# Signal_Conditioner.net
KiCad netlist of a schematic drawn in Altium Designer
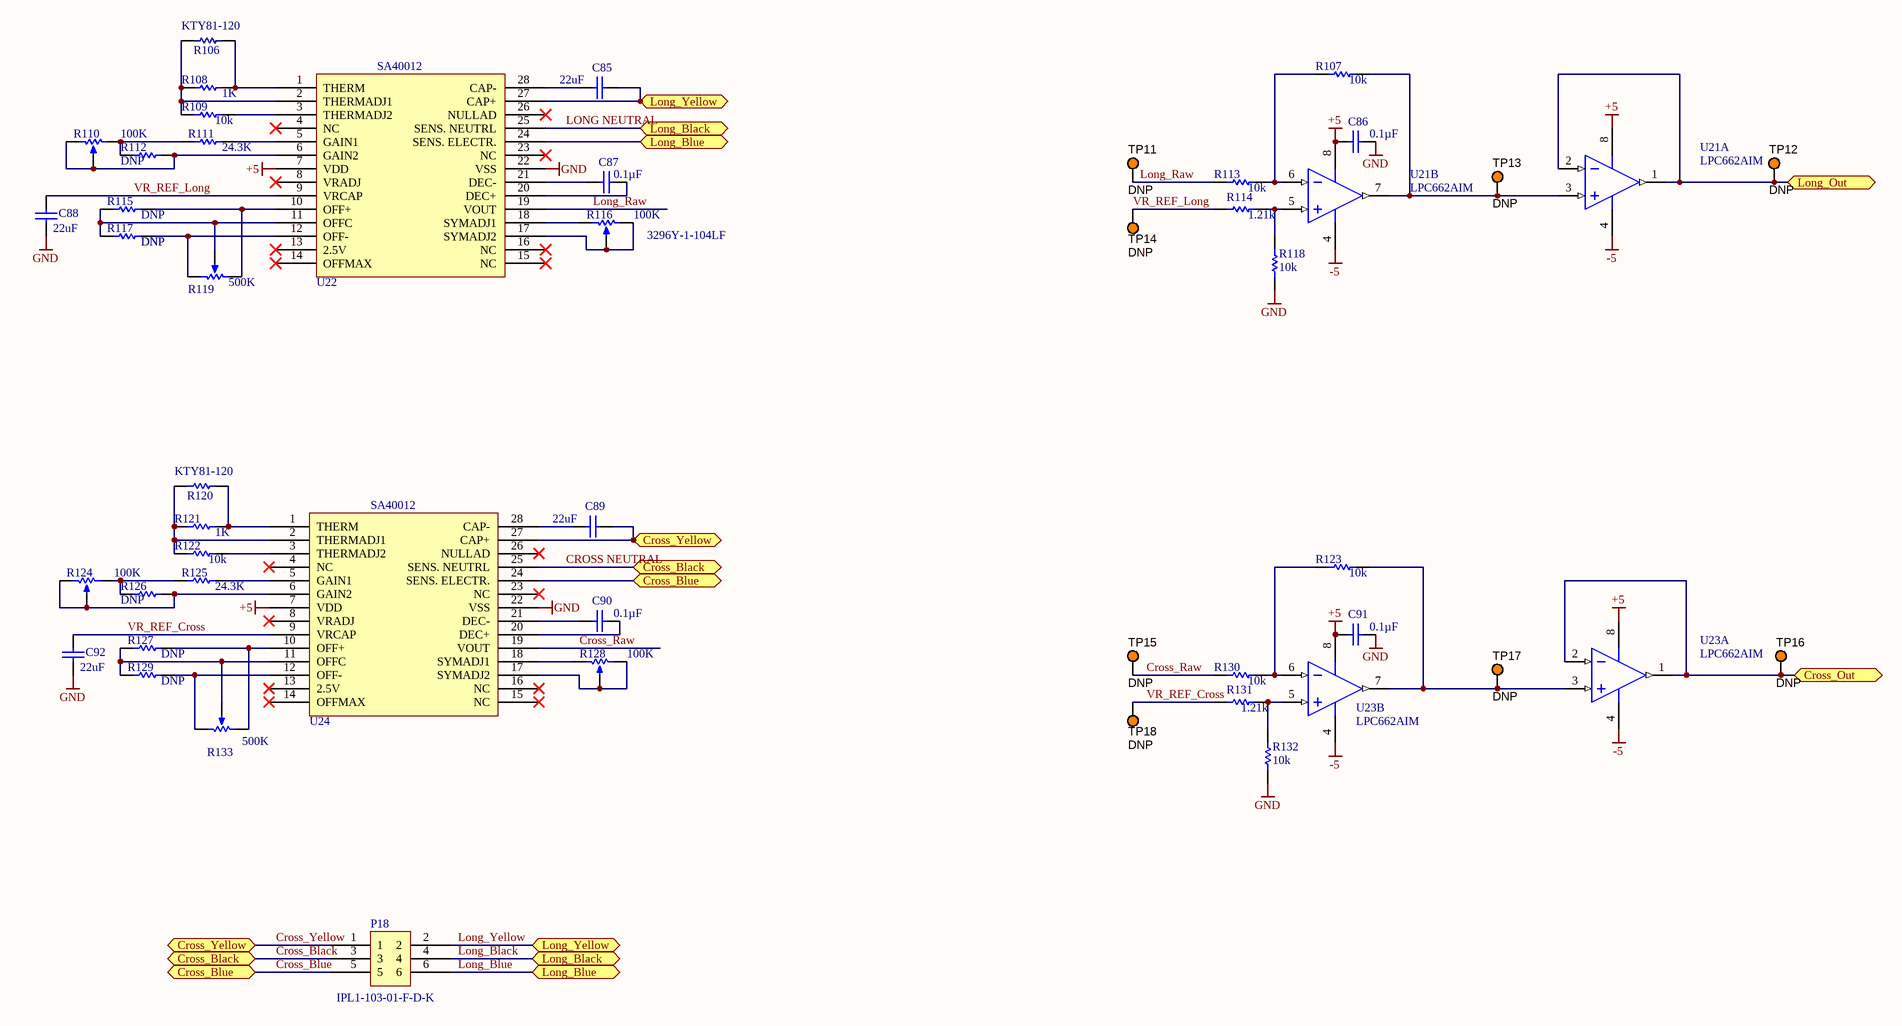
[diagram p0: Signal_Conditioner.SchDoc]

(export (version "E")
  (design (tool "Eeschema 10.0.6"))
  (components
    (comp (ref "C85")
      (value "22uF")
      (footprint "CAPC0805(2012)145_N")
      (description "CAP CER 22UF 16V X5R 0805")
      (fields
        (field (name "MANUFACTURER") "Murata Electronics North America")
        (field (name "MANUFACTURER PART NUMBER") "GRM219R61C226ME15L")
      )
      (libsource (lib "Altium Content Vault") (part "CMP-1036-04795-1"))
    )
    (comp (ref "C86")
      (value "CAP CER 0.1UF 25V X7R 0805")
      (footprint "CAPC0805(2012)145_N")
      (fields
        (field (name "MANUFACTURER") "Murata Electronics North America")
        (field (name "MANUFACTURER PART NUMBER") "GRM21BR71E104KA01L")
        (field (name "CAPACITANCE") "0.1µF")
        (field (name "TOLERANCE") "±10%")
      )
      (libsource (lib "Altium Content Vault") (part "CMP-1036-04795-1"))
    )
    (comp (ref "C87")
      (value "CAP CER 0.1UF 25V X7R 0805")
      (footprint "CAPC0805(2012)145_N")
      (fields
        (field (name "MANUFACTURER") "Murata Electronics North America")
        (field (name "MANUFACTURER PART NUMBER") "GRM21BR71E104KA01L")
        (field (name "CAPACITANCE") "0.1µF")
        (field (name "TOLERANCE") "±10%")
      )
      (libsource (lib "Altium Content Vault") (part "CMP-1036-04795-1"))
    )
    (comp (ref "C88")
      (value "22uF")
      (footprint "CAPC0805(2012)145_N")
      (description "CAP CER 22UF 16V X5R 0805")
      (fields
        (field (name "MANUFACTURER") "Murata Electronics North America")
        (field (name "MANUFACTURER PART NUMBER") "GRM219R61C226ME15L")
      )
      (libsource (lib "Altium Content Vault") (part "CMP-1036-04795-1"))
    )
    (comp (ref "C89")
      (value "22uF")
      (footprint "CAPC0805(2012)145_N")
      (description "CAP CER 22UF 16V X5R 0805")
      (fields
        (field (name "MANUFACTURER") "Murata Electronics North America")
        (field (name "MANUFACTURER PART NUMBER") "GRM219R61C226ME15L")
      )
      (libsource (lib "Altium Content Vault") (part "CMP-1036-04795-1"))
    )
    (comp (ref "C90")
      (value "CAP CER 0.1UF 25V X7R 0805")
      (footprint "CAPC0805(2012)145_N")
      (fields
        (field (name "MANUFACTURER") "Murata Electronics North America")
        (field (name "MANUFACTURER PART NUMBER") "GRM21BR71E104KA01L")
        (field (name "CAPACITANCE") "0.1µF")
        (field (name "TOLERANCE") "±10%")
      )
      (libsource (lib "Altium Content Vault") (part "CMP-1036-04795-1"))
    )
    (comp (ref "C91")
      (value "CAP CER 0.1UF 25V X7R 0805")
      (footprint "CAPC0805(2012)145_N")
      (fields
        (field (name "MANUFACTURER") "Murata Electronics North America")
        (field (name "MANUFACTURER PART NUMBER") "GRM21BR71E104KA01L")
        (field (name "CAPACITANCE") "0.1µF")
        (field (name "TOLERANCE") "±10%")
      )
      (libsource (lib "Altium Content Vault") (part "CMP-1036-04795-1"))
    )
    (comp (ref "C92")
      (value "22uF")
      (footprint "CAPC0805(2012)145_N")
      (description "CAP CER 22UF 16V X5R 0805")
      (fields
        (field (name "MANUFACTURER") "Murata Electronics North America")
        (field (name "MANUFACTURER PART NUMBER") "GRM219R61C226ME15L")
      )
      (libsource (lib "Altium Content Vault") (part "CMP-1036-04795-1"))
    )
    (comp (ref "P18")
      (value "IPL1-103-01-F-D")
      (footprint "IPL1-103-01-F-D")
      (fields
        (field (name "MANUFACTURER") "SAMTEC")
        (field (name "MANUFACTURER PART NUMBER") "IPL1-103-01-F-D-K")
        (field (name "COMPONENTLINK1URL") "https://webassistants.partcommunity.com/23d-libs/samtec/search/resolve.html?EMAIL=mysamtec@samtec.com&PN=HTSW-114-05-F-D")
        (field (name "COMPONENTLINK1DESCRIPTION") "https://webassistants.partcommunity.com/23d-libs/samtec/search/resolve.html?EMAIL=mysamtec@samtec.com&PN=HTSW-114-05-F-D")
      )
      (libsource (lib "ZLS_Schematic_lib") (part "IPL1-103-01-F-D"))
    )
    (comp (ref "R106")
      (value "KTY81-120")
      (footprint "KTY81-120")
      (description "THERMISTOR PTC 1K OHM PBCYT2")
      (fields
        (field (name "MANUFACTURER") "NXP USA Inc.")
        (field (name "MANUFACTURER PART NUMBER") "KTY81/120,112")
      )
      (libsource (lib "ZLS_Schematic_lib") (part "KTY81-120"))
    )
    (comp (ref "R107")
      (value "10k")
      (footprint "RESC0805(2012)_L")
      (description "RES SMD 10K OHM 1% 1/8W 0805")
      (fields
        (field (name "MANUFACTURER") "Vishay Dale")
        (field (name "MANUFACTURER PART NUMBER") "CRCW080510K0FKEA")
      )
      (libsource (lib "Altium Content Vault") (part "CMP-1013-00393-1"))
    )
    (comp (ref "R108")
      (value "1K")
      (footprint "RESC0805(2012)_L")
      (description "RES SMD 1K OHM 1% 1/8W 0805")
      (fields
        (field (name "MANUFACTURER") "Vishay Dale")
        (field (name "MANUFACTURER PART NUMBER") "CRCW08051K00FKEA")
      )
      (libsource (lib "Altium Content Vault") (part "CMP-1013-00393-1"))
    )
    (comp (ref "R109")
      (value "10k")
      (footprint "RESC0805(2012)_L")
      (description "RES SMD 10K OHM 1% 1/8W 0805")
      (fields
        (field (name "MANUFACTURER") "Vishay Dale")
        (field (name "MANUFACTURER PART NUMBER") "CRCW080510K0FKEA")
      )
      (libsource (lib "Altium Content Vault") (part "CMP-1013-00393-1"))
    )
    (comp (ref "R110")
      (value "100K")
      (footprint "Trimmer 2.54")
      (description "TRIMMER 5K OHM 0.25W PC PIN")
      (fields
        (field (name "MANUFACTURER") "Bourns Inc.")
        (field (name "MANUFACTURER PART NUMBER") "3296Y-1-104LF")
      )
      (libsource (lib "ZLS_Schematic_lib") (part "Trimmer"))
    )
    (comp (ref "R111")
      (value "24.3K")
      (footprint "RESC0805(2012)_L")
      (description "RES SMD 24.3K OHM 1% 1/8W 0805")
      (fields
        (field (name "MANUFACTURER") "Vishay Dale")
        (field (name "MANUFACTURER PART NUMBER") "CRCW080524K3FKEA")
      )
      (libsource (lib "Altium Content Vault") (part "CMP-1013-00393-1"))
    )
    (comp (ref "R112")
      (value "DNP")
      (footprint "RESC0805(2012)_L")
      (description "RES SMD 10K OHM 1% 1/8W 0805")
      (fields
        (field (name "MANUFACTURER") "Vishay Dale")
        (field (name "MANUFACTURER PART NUMBER") "CRCW080510K0FKEA")
      )
      (libsource (lib "Altium Content Vault") (part "CMP-1013-00393-1"))
    )
    (comp (ref "R113")
      (value "10k")
      (footprint "RESC0805(2012)_L")
      (description "RES SMD 10K OHM 1% 1/8W 0805")
      (fields
        (field (name "MANUFACTURER") "Vishay Dale")
        (field (name "MANUFACTURER PART NUMBER") "CRCW080510K0FKEA")
      )
      (libsource (lib "Altium Content Vault") (part "CMP-1013-00393-1"))
    )
    (comp (ref "R114")
      (value "1.21k")
      (footprint "RESC0805(2012)_L")
      (description "RES SMD 1.21K OHM 1% 1/8W 0805")
      (fields
        (field (name "MANUFACTURER") "Vishay Dale")
        (field (name "MANUFACTURER PART NUMBER") "CRCW08051K21FKEA")
      )
      (libsource (lib "Altium Content Vault") (part "CMP-1013-00393-1"))
    )
    (comp (ref "R115")
      (value "DNP")
      (footprint "RESC0805(2012)_L")
      (description "RES SMD 249K OHM 1% 1/8W 0805")
      (fields
        (field (name "MANUFACTURER") "Vishay Dale")
        (field (name "MANUFACTURER PART NUMBER") "CRCW0805249KFKECC")
      )
      (libsource (lib "Altium Content Vault") (part "CMP-1013-00393-1"))
    )
    (comp (ref "R116")
      (value "100K")
      (footprint "Trimmer 2.54")
      (description "TRIMMER 5K OHM 0.25W PC PIN")
      (fields
        (field (name "MANUFACTURER") "Bourns Inc.")
        (field (name "MANUFACTURER PART NUMBER") "3296Y-1-104LF")
      )
      (libsource (lib "ZLS_Schematic_lib") (part "Trimmer"))
    )
    (comp (ref "R117")
      (value "DNP")
      (footprint "RESC0805(2012)_L")
      (description "RES SMD 249K OHM 1% 1/8W 0805")
      (fields
        (field (name "MANUFACTURER") "Vishay Dale")
        (field (name "MANUFACTURER PART NUMBER") "CRCW0805249KFKECC")
      )
      (libsource (lib "Altium Content Vault") (part "CMP-1013-00393-1"))
    )
    (comp (ref "R118")
      (value "10k")
      (footprint "RESC0805(2012)_L")
      (description "RES SMD 10K OHM 1% 1/8W 0805")
      (fields
        (field (name "MANUFACTURER") "Vishay Dale")
        (field (name "MANUFACTURER PART NUMBER") "CRCW080510K0FKEA")
      )
      (libsource (lib "Altium Content Vault") (part "CMP-1013-00393-1"))
    )
    (comp (ref "R119")
      (value "500K")
      (footprint "Trimmer 2.54")
      (description "TRIMMER 500K OHM 0.5W PC PIN TOP")
      (fields
        (field (name "MANUFACTURER") "Bourns Inc.")
        (field (name "MANUFACTURER PART NUMBER") "3296Y-1-504LF")
      )
      (libsource (lib "ZLS_Schematic_lib") (part "Trimmer"))
    )
    (comp (ref "R120")
      (value "KTY81-120")
      (footprint "KTY81-120")
      (description "THERMISTOR PTC 1K OHM PBCYT2")
      (fields
        (field (name "MANUFACTURER") "NXP USA Inc.")
        (field (name "MANUFACTURER PART NUMBER") "KTY81/120,112")
      )
      (libsource (lib "ZLS_Schematic_lib") (part "KTY81-120"))
    )
    (comp (ref "R121")
      (value "1K")
      (footprint "RESC0805(2012)_L")
      (description "RES SMD 1K OHM 1% 1/8W 0805")
      (fields
        (field (name "MANUFACTURER") "Vishay Dale")
        (field (name "MANUFACTURER PART NUMBER") "CRCW08051K00FKEA")
      )
      (libsource (lib "Altium Content Vault") (part "CMP-1013-00393-1"))
    )
    (comp (ref "R122")
      (value "10k")
      (footprint "RESC0805(2012)_L")
      (description "RES SMD 10K OHM 1% 1/8W 0805")
      (fields
        (field (name "MANUFACTURER") "Vishay Dale")
        (field (name "MANUFACTURER PART NUMBER") "CRCW080510K0FKEA")
      )
      (libsource (lib "Altium Content Vault") (part "CMP-1013-00393-1"))
    )
    (comp (ref "R123")
      (value "10k")
      (footprint "RESC0805(2012)_L")
      (description "RES SMD 10K OHM 1% 1/8W 0805")
      (fields
        (field (name "MANUFACTURER") "Vishay Dale")
        (field (name "MANUFACTURER PART NUMBER") "CRCW080510K0FKEA")
      )
      (libsource (lib "Altium Content Vault") (part "CMP-1013-00393-1"))
    )
    (comp (ref "R124")
      (value "100K")
      (footprint "Trimmer 2.54")
      (description "TRIMMER 5K OHM 0.25W PC PIN")
      (fields
        (field (name "MANUFACTURER") "Bourns Inc.")
        (field (name "MANUFACTURER PART NUMBER") "3296Y-1-104LF")
      )
      (libsource (lib "ZLS_Schematic_lib") (part "Trimmer"))
    )
    (comp (ref "R125")
      (value "24.3K")
      (footprint "RESC0805(2012)_L")
      (description "RES SMD 24.3K OHM 1% 1/8W 0805")
      (fields
        (field (name "MANUFACTURER") "Vishay Dale")
        (field (name "MANUFACTURER PART NUMBER") "CRCW080524K3FKEA")
      )
      (libsource (lib "Altium Content Vault") (part "CMP-1013-00393-1"))
    )
    (comp (ref "R126")
      (value "DNP")
      (footprint "RESC0805(2012)_L")
      (description "RES SMD 10K OHM 1% 1/8W 0805")
      (fields
        (field (name "MANUFACTURER") "Vishay Dale")
        (field (name "MANUFACTURER PART NUMBER") "CRCW080510K0FKEA")
      )
      (libsource (lib "Altium Content Vault") (part "CMP-1013-00393-1"))
    )
    (comp (ref "R127")
      (value "DNP")
      (footprint "RESC0805(2012)_L")
      (description "RES SMD 249K OHM 1% 1/8W 0805")
      (fields
        (field (name "MANUFACTURER") "Vishay Dale")
        (field (name "MANUFACTURER PART NUMBER") "CRCW0805249KFKECC")
      )
      (libsource (lib "Altium Content Vault") (part "CMP-1013-00393-1"))
    )
    (comp (ref "R128")
      (value "100K")
      (footprint "Trimmer 2.54")
      (description "TRIMMER 5K OHM 0.25W PC PIN")
      (fields
        (field (name "MANUFACTURER") "Bourns Inc.")
        (field (name "MANUFACTURER PART NUMBER") "3296Y-1-104LF")
      )
      (libsource (lib "ZLS_Schematic_lib") (part "Trimmer"))
    )
    (comp (ref "R129")
      (value "DNP")
      (footprint "RESC0805(2012)_L")
      (description "RES SMD 249K OHM 1% 1/8W 0805")
      (fields
        (field (name "MANUFACTURER") "Vishay Dale")
        (field (name "MANUFACTURER PART NUMBER") "CRCW0805249KFKECC")
      )
      (libsource (lib "Altium Content Vault") (part "CMP-1013-00393-1"))
    )
    (comp (ref "R130")
      (value "10k")
      (footprint "RESC0805(2012)_L")
      (description "RES SMD 10K OHM 1% 1/8W 0805")
      (fields
        (field (name "MANUFACTURER") "Vishay Dale")
        (field (name "MANUFACTURER PART NUMBER") "CRCW080510K0FKEA")
      )
      (libsource (lib "Altium Content Vault") (part "CMP-1013-00393-1"))
    )
    (comp (ref "R131")
      (value "1.21k")
      (footprint "RESC0805(2012)_L")
      (description "RES SMD 1.21K OHM 1% 1/8W 0805")
      (fields
        (field (name "MANUFACTURER") "Vishay Dale")
        (field (name "MANUFACTURER PART NUMBER") "CRCW08051K21FKEA")
      )
      (libsource (lib "Altium Content Vault") (part "CMP-1013-00393-1"))
    )
    (comp (ref "R132")
      (value "10k")
      (footprint "RESC0805(2012)_L")
      (description "RES SMD 10K OHM 1% 1/8W 0805")
      (fields
        (field (name "MANUFACTURER") "Vishay Dale")
        (field (name "MANUFACTURER PART NUMBER") "CRCW080510K0FKEA")
      )
      (libsource (lib "Altium Content Vault") (part "CMP-1013-00393-1"))
    )
    (comp (ref "R133")
      (value "500K")
      (footprint "Trimmer 2.54")
      (description "TRIMMER 500K OHM 0.5W PC PIN TOP")
      (fields
        (field (name "MANUFACTURER") "Bourns Inc.")
        (field (name "MANUFACTURER PART NUMBER") "3296Y-1-504LF")
      )
      (libsource (lib "ZLS_Schematic_lib") (part "Trimmer"))
    )
    (comp (ref "TP11")
      (value "DNP")
      (footprint "KSTN-5003")
      (description "Test Point, Orange, 1-Pin THD, RoHS")
      (fields
        (field (name "MANUFACTURER") "Keystone Electronics")
        (field (name "MANUFACTURER PART NUMBER") "5003")
      )
      (libsource (lib "Altium Content Vault") (part "CMP-1672-00009-1"))
    )
    (comp (ref "TP12")
      (value "DNP")
      (footprint "KSTN-5003")
      (description "Test Point, Orange, 1-Pin THD, RoHS")
      (fields
        (field (name "MANUFACTURER") "Keystone Electronics")
        (field (name "MANUFACTURER PART NUMBER") "5003")
      )
      (libsource (lib "Altium Content Vault") (part "CMP-1672-00009-1"))
    )
    (comp (ref "TP13")
      (value "DNP")
      (footprint "KSTN-5003")
      (description "Test Point, Orange, 1-Pin THD, RoHS")
      (fields
        (field (name "MANUFACTURER") "Keystone Electronics")
        (field (name "MANUFACTURER PART NUMBER") "5003")
      )
      (libsource (lib "Altium Content Vault") (part "CMP-1672-00009-1"))
    )
    (comp (ref "TP14")
      (value "DNP")
      (footprint "KSTN-5003")
      (description "Test Point, Orange, 1-Pin THD, RoHS")
      (fields
        (field (name "MANUFACTURER") "Keystone Electronics")
        (field (name "MANUFACTURER PART NUMBER") "5003")
      )
      (libsource (lib "Altium Content Vault") (part "CMP-1672-00009-1"))
    )
    (comp (ref "TP15")
      (value "DNP")
      (footprint "KSTN-5003")
      (description "Test Point, Orange, 1-Pin THD, RoHS")
      (fields
        (field (name "MANUFACTURER") "Keystone Electronics")
        (field (name "MANUFACTURER PART NUMBER") "5003")
      )
      (libsource (lib "Altium Content Vault") (part "CMP-1672-00009-1"))
    )
    (comp (ref "TP16")
      (value "DNP")
      (footprint "KSTN-5003")
      (description "Test Point, Orange, 1-Pin THD, RoHS")
      (fields
        (field (name "MANUFACTURER") "Keystone Electronics")
        (field (name "MANUFACTURER PART NUMBER") "5003")
      )
      (libsource (lib "Altium Content Vault") (part "CMP-1672-00009-1"))
    )
    (comp (ref "TP17")
      (value "DNP")
      (footprint "KSTN-5003")
      (description "Test Point, Orange, 1-Pin THD, RoHS")
      (fields
        (field (name "MANUFACTURER") "Keystone Electronics")
        (field (name "MANUFACTURER PART NUMBER") "5003")
      )
      (libsource (lib "Altium Content Vault") (part "CMP-1672-00009-1"))
    )
    (comp (ref "TP18")
      (value "DNP")
      (footprint "KSTN-5003")
      (description "Test Point, Orange, 1-Pin THD, RoHS")
      (fields
        (field (name "MANUFACTURER") "Keystone Electronics")
        (field (name "MANUFACTURER PART NUMBER") "5003")
      )
      (libsource (lib "Altium Content Vault") (part "CMP-1672-00009-1"))
    )
    (comp (ref "U21")
      (value "LPC662AIM")
      (footprint "D0008A_M")
      (description "Low Power CMOS Dual Operational Amplifier, 8-pin Narrow SOIC")
      (fields (field (name "MANUFACTURER") "Texas Instruments"))
      (libsource (lib "Altium Content Vault") (part "AMP-OPA-LM6132-8"))
    )
    (comp (ref "U22")
      (value "SA40012")
      (footprint "SA40012")
      (description "Single Axix CMOS Signal Conditioning Module")
      (fields (field (name "MANUFACTURER") "Spectron") (field (name "MANUFACTURER PART NUMBER") "A40012"))
      (libsource (lib "ZLS_Schematic_lib") (part "SA40012"))
    )
    (comp (ref "U23")
      (value "LPC662AIM")
      (footprint "D0008A_M")
      (description "Low Power CMOS Dual Operational Amplifier, 8-pin Narrow SOIC")
      (fields
        (field (name "MANUFACTURER") "Texas Instruments")
        (field (name "MANUFACTURER PART NUMBER") "LPC662AIMX/NOPB")
      )
      (libsource (lib "Altium Content Vault") (part "CMP-0055-00867-3"))
    )
    (comp (ref "U24")
      (value "SA40012")
      (footprint "SA40012")
      (description "Single Axix CMOS Signal Conditioning Module")
      (fields (field (name "MANUFACTURER") "Spectron") (field (name "MANUFACTURER PART NUMBER") "A40012"))
      (libsource (lib "ZLS_Schematic_lib") (part "SA40012"))
    )
  )
  (nets
    (net (code "1") (name "+5") (class "Default")
      (node (ref "C86") (pin "1") (pinfunction "1_1") (pintype "passive"))
      (node (ref "C91") (pin "1") (pinfunction "1_1") (pintype "passive"))
      (node (ref "U21") (pin "8") (pinfunction "V+_8") (pintype "power_in"))
      (node (ref "U22") (pin "7") (pinfunction "VDD_7") (pintype "passive"))
      (node (ref "U23") (pin "8") (pinfunction "V+_8") (pintype "power_in"))
      (node (ref "U24") (pin "7") (pinfunction "VDD_7") (pintype "passive"))
    )
    (net (code "2") (name "-5") (class "Default")
      (node (ref "U21") (pin "4") (pinfunction "V-_4") (pintype "power_in"))
      (node (ref "U23") (pin "4") (pinfunction "V-_4") (pintype "power_in"))
    )
    (net (code "3") (name "/CROSS NEUTRAL") (class "Default")
      (node (ref "P18") (pin "3") (pinfunction "3_3") (pintype "passive"))
      (node (ref "U24") (pin "25") (pinfunction "SENS._NEUTRL_25") (pintype "passive"))
    )
    (net (code "4") (name "/Cross_Blue") (class "Default")
      (node (ref "P18") (pin "5") (pinfunction "5_5") (pintype "passive"))
      (node (ref "U24") (pin "24") (pinfunction "SENS._ELECTR._24") (pintype "passive"))
    )
    (net (code "5") (name "/Cross_Out") (class "Default")
      (node (ref "TP16") (pin "1") (pinfunction "1_1") (pintype "passive"))
      (node (ref "U23") (pin "1") (pinfunction "OUTA_1") (pintype "output"))
      (node (ref "U23") (pin "2") (pinfunction "INA-_2") (pintype "input"))
    )
    (net (code "6") (name "/Cross_Raw") (class "Default")
      (node (ref "R130") (pin "1") (pinfunction "1_1") (pintype "passive"))
      (node (ref "TP15") (pin "1") (pinfunction "1_1") (pintype "passive"))
      (node (ref "U24") (pin "19") (pinfunction "VOUT_19") (pintype "passive"))
    )
    (net (code "7") (name "/Cross_Yellow") (class "Default")
      (node (ref "C89") (pin "2") (pinfunction "2_2") (pintype "passive"))
      (node (ref "P18") (pin "1") (pinfunction "1_1") (pintype "passive"))
      (node (ref "U24") (pin "27") (pinfunction "CAP+_27") (pintype "passive"))
    )
    (net (code "8") (name "/LONG NEUTRAL") (class "Default")
      (node (ref "P18") (pin "4") (pinfunction "4_4") (pintype "passive"))
      (node (ref "U22") (pin "25") (pinfunction "SENS._NEUTRL_25") (pintype "passive"))
    )
    (net (code "9") (name "/Long_Blue") (class "Default")
      (node (ref "P18") (pin "6") (pinfunction "6_6") (pintype "passive"))
      (node (ref "U22") (pin "24") (pinfunction "SENS._ELECTR._24") (pintype "passive"))
    )
    (net (code "10") (name "/Long_Out") (class "Default")
      (node (ref "TP12") (pin "1") (pinfunction "1_1") (pintype "passive"))
      (node (ref "U21") (pin "1") (pinfunction "OUTA_1") (pintype "output"))
      (node (ref "U21") (pin "2") (pinfunction "INA-_2") (pintype "input"))
    )
    (net (code "11") (name "/Long_Raw") (class "Default")
      (node (ref "R113") (pin "1") (pinfunction "1_1") (pintype "passive"))
      (node (ref "TP11") (pin "1") (pinfunction "1_1") (pintype "passive"))
      (node (ref "U22") (pin "19") (pinfunction "VOUT_19") (pintype "passive"))
    )
    (net (code "12") (name "/Long_Yellow") (class "Default")
      (node (ref "C85") (pin "2") (pinfunction "2_2") (pintype "passive"))
      (node (ref "P18") (pin "2") (pinfunction "2_2") (pintype "passive"))
      (node (ref "U22") (pin "27") (pinfunction "CAP+_27") (pintype "passive"))
    )
    (net (code "13") (name "/VR_REF_Cross") (class "Default")
      (node (ref "C92") (pin "1") (pinfunction "1_1") (pintype "passive"))
      (node (ref "R131") (pin "2") (pinfunction "2_2") (pintype "passive"))
      (node (ref "TP18") (pin "1") (pinfunction "1_1") (pintype "passive"))
      (node (ref "U24") (pin "9") (pinfunction "VRCAP_9") (pintype "passive"))
    )
    (net (code "14") (name "/VR_REF_Long") (class "Default")
      (node (ref "C88") (pin "1") (pinfunction "1_1") (pintype "passive"))
      (node (ref "R114") (pin "2") (pinfunction "2_2") (pintype "passive"))
      (node (ref "TP14") (pin "1") (pinfunction "1_1") (pintype "passive"))
      (node (ref "U22") (pin "9") (pinfunction "VRCAP_9") (pintype "passive"))
    )
    (net (code "15") (name "GND") (class "Default")
      (node (ref "C86") (pin "2") (pinfunction "2_2") (pintype "passive"))
      (node (ref "C88") (pin "2") (pinfunction "2_2") (pintype "passive"))
      (node (ref "C91") (pin "2") (pinfunction "2_2") (pintype "passive"))
      (node (ref "C92") (pin "2") (pinfunction "2_2") (pintype "passive"))
      (node (ref "R118") (pin "1") (pinfunction "1_1") (pintype "passive"))
      (node (ref "R132") (pin "1") (pinfunction "1_1") (pintype "passive"))
      (node (ref "U22") (pin "22") (pinfunction "VSS_22") (pintype "passive"))
      (node (ref "U24") (pin "22") (pinfunction "VSS_22") (pintype "passive"))
    )
    (net (code "16") (name "Net-(R110-a)") (class "Default")
      (node (ref "R110") (pin "1") (pinfunction "a_1") (pintype "passive"))
      (node (ref "R110") (pin "2") (pinfunction "b_2") (pintype "passive"))
      (node (ref "R112") (pin "2") (pinfunction "2_2") (pintype "passive"))
      (node (ref "U22") (pin "6") (pinfunction "GAIN2_6") (pintype "passive"))
    )
    (net (code "17") (name "Net-(R110-c)") (class "Default")
      (node (ref "R110") (pin "3") (pinfunction "c_3") (pintype "passive"))
      (node (ref "R111") (pin "1") (pinfunction "1_1") (pintype "passive"))
      (node (ref "R112") (pin "1") (pinfunction "1_1") (pintype "passive"))
    )
    (net (code "18") (name "Net-(R116-a)") (class "Default")
      (node (ref "R116") (pin "1") (pinfunction "a_1") (pintype "passive"))
      (node (ref "U22") (pin "18") (pinfunction "SYMADJ1_18") (pintype "passive"))
    )
    (net (code "19") (name "Net-(R116-b)") (class "Default")
      (node (ref "R116") (pin "2") (pinfunction "b_2") (pintype "passive"))
      (node (ref "R116") (pin "3") (pinfunction "c_3") (pintype "passive"))
      (node (ref "U22") (pin "17") (pinfunction "SYMADJ2_17") (pintype "passive"))
    )
    (net (code "20") (name "Net-(R119-a)") (class "Default")
      (node (ref "R115") (pin "2") (pinfunction "2_2") (pintype "passive"))
      (node (ref "R119") (pin "1") (pinfunction "a_1") (pintype "passive"))
      (node (ref "U22") (pin "10") (pinfunction "OFF+_10") (pintype "passive"))
    )
    (net (code "21") (name "Net-(R119-b)") (class "Default")
      (node (ref "R115") (pin "1") (pinfunction "1_1") (pintype "passive"))
      (node (ref "R117") (pin "1") (pinfunction "1_1") (pintype "passive"))
      (node (ref "R119") (pin "2") (pinfunction "b_2") (pintype "passive"))
      (node (ref "U22") (pin "11") (pinfunction "OFFC_11") (pintype "passive"))
    )
    (net (code "22") (name "Net-(R119-c)") (class "Default")
      (node (ref "R117") (pin "2") (pinfunction "2_2") (pintype "passive"))
      (node (ref "R119") (pin "3") (pinfunction "c_3") (pintype "passive"))
      (node (ref "U22") (pin "12") (pinfunction "OFF-_12") (pintype "passive"))
    )
    (net (code "23") (name "Net-(R124-a)") (class "Default")
      (node (ref "R124") (pin "1") (pinfunction "a_1") (pintype "passive"))
      (node (ref "R124") (pin "2") (pinfunction "b_2") (pintype "passive"))
      (node (ref "R126") (pin "2") (pinfunction "2_2") (pintype "passive"))
      (node (ref "U24") (pin "6") (pinfunction "GAIN2_6") (pintype "passive"))
    )
    (net (code "24") (name "Net-(R124-c)") (class "Default")
      (node (ref "R124") (pin "3") (pinfunction "c_3") (pintype "passive"))
      (node (ref "R125") (pin "1") (pinfunction "1_1") (pintype "passive"))
      (node (ref "R126") (pin "1") (pinfunction "1_1") (pintype "passive"))
    )
    (net (code "25") (name "Net-(R128-a)") (class "Default")
      (node (ref "R128") (pin "1") (pinfunction "a_1") (pintype "passive"))
      (node (ref "U24") (pin "18") (pinfunction "SYMADJ1_18") (pintype "passive"))
    )
    (net (code "26") (name "Net-(R128-b)") (class "Default")
      (node (ref "R128") (pin "2") (pinfunction "b_2") (pintype "passive"))
      (node (ref "R128") (pin "3") (pinfunction "c_3") (pintype "passive"))
      (node (ref "U24") (pin "17") (pinfunction "SYMADJ2_17") (pintype "passive"))
    )
    (net (code "27") (name "Net-(R133-a)") (class "Default")
      (node (ref "R127") (pin "2") (pinfunction "2_2") (pintype "passive"))
      (node (ref "R133") (pin "1") (pinfunction "a_1") (pintype "passive"))
      (node (ref "U24") (pin "10") (pinfunction "OFF+_10") (pintype "passive"))
    )
    (net (code "28") (name "Net-(R133-b)") (class "Default")
      (node (ref "R127") (pin "1") (pinfunction "1_1") (pintype "passive"))
      (node (ref "R129") (pin "1") (pinfunction "1_1") (pintype "passive"))
      (node (ref "R133") (pin "2") (pinfunction "b_2") (pintype "passive"))
      (node (ref "U24") (pin "11") (pinfunction "OFFC_11") (pintype "passive"))
    )
    (net (code "29") (name "Net-(R133-c)") (class "Default")
      (node (ref "R129") (pin "2") (pinfunction "2_2") (pintype "passive"))
      (node (ref "R133") (pin "3") (pinfunction "c_3") (pintype "passive"))
      (node (ref "U24") (pin "12") (pinfunction "OFF-_12") (pintype "passive"))
    )
    (net (code "30") (name "Net-(U21A-INA+)") (class "Default")
      (node (ref "R107") (pin "2") (pinfunction "2_2") (pintype "passive"))
      (node (ref "TP13") (pin "1") (pinfunction "1_1") (pintype "passive"))
      (node (ref "U21") (pin "3") (pinfunction "INA+_3") (pintype "input"))
      (node (ref "U21") (pin "7") (pinfunction "OUTB_7") (pintype "output"))
    )
    (net (code "31") (name "Net-(U21B-INB+)") (class "Default")
      (node (ref "R114") (pin "1") (pinfunction "1_1") (pintype "passive"))
      (node (ref "R118") (pin "2") (pinfunction "2_2") (pintype "passive"))
      (node (ref "U21") (pin "5") (pinfunction "INB+_5") (pintype "input"))
    )
    (net (code "32") (name "Net-(U21B-INB-)") (class "Default")
      (node (ref "R107") (pin "1") (pinfunction "1_1") (pintype "passive"))
      (node (ref "R113") (pin "2") (pinfunction "2_2") (pintype "passive"))
      (node (ref "U21") (pin "6") (pinfunction "INB-_6") (pintype "input"))
    )
    (net (code "33") (name "Net-(U22-CAP-)") (class "Default")
      (node (ref "C85") (pin "1") (pinfunction "1_1") (pintype "passive"))
      (node (ref "U22") (pin "28") (pinfunction "CAP-_28") (pintype "passive"))
    )
    (net (code "34") (name "Net-(U22-DEC+)") (class "Default")
      (node (ref "C87") (pin "2") (pinfunction "2_2") (pintype "passive"))
      (node (ref "U22") (pin "20") (pinfunction "DEC+_20") (pintype "passive"))
    )
    (net (code "35") (name "Net-(U22-DEC-)") (class "Default")
      (node (ref "C87") (pin "1") (pinfunction "1_1") (pintype "passive"))
      (node (ref "U22") (pin "21") (pinfunction "DEC-_21") (pintype "passive"))
    )
    (net (code "36") (name "Net-(U22-GAIN1)") (class "Default")
      (node (ref "R111") (pin "2") (pinfunction "2_2") (pintype "passive"))
      (node (ref "U22") (pin "5") (pinfunction "GAIN1_5") (pintype "passive"))
    )
    (net (code "37") (name "Net-(U22-THERM)") (class "Default")
      (node (ref "R106") (pin "2") (pinfunction "2_2") (pintype "passive"))
      (node (ref "R108") (pin "2") (pinfunction "2_2") (pintype "passive"))
      (node (ref "U22") (pin "1") (pinfunction "THERM_1") (pintype "passive"))
    )
    (net (code "38") (name "Net-(U22-THERMADJ1)") (class "Default")
      (node (ref "R106") (pin "1") (pinfunction "1_1") (pintype "passive"))
      (node (ref "R108") (pin "1") (pinfunction "1_1") (pintype "passive"))
      (node (ref "R109") (pin "1") (pinfunction "1_1") (pintype "passive"))
      (node (ref "U22") (pin "2") (pinfunction "THERMADJ1_2") (pintype "passive"))
    )
    (net (code "39") (name "Net-(U22-THERMADJ2)") (class "Default")
      (node (ref "R109") (pin "2") (pinfunction "2_2") (pintype "passive"))
      (node (ref "U22") (pin "3") (pinfunction "THERMADJ2_3") (pintype "passive"))
    )
    (net (code "40") (name "Net-(U23A-INA+)") (class "Default")
      (node (ref "R123") (pin "2") (pinfunction "2_2") (pintype "passive"))
      (node (ref "TP17") (pin "1") (pinfunction "1_1") (pintype "passive"))
      (node (ref "U23") (pin "3") (pinfunction "INA+_3") (pintype "input"))
      (node (ref "U23") (pin "7") (pinfunction "OUTB_7") (pintype "output"))
    )
    (net (code "41") (name "Net-(U23B-INB+)") (class "Default")
      (node (ref "R131") (pin "1") (pinfunction "1_1") (pintype "passive"))
      (node (ref "R132") (pin "2") (pinfunction "2_2") (pintype "passive"))
      (node (ref "U23") (pin "5") (pinfunction "INB+_5") (pintype "input"))
    )
    (net (code "42") (name "Net-(U23B-INB-)") (class "Default")
      (node (ref "R123") (pin "1") (pinfunction "1_1") (pintype "passive"))
      (node (ref "R130") (pin "2") (pinfunction "2_2") (pintype "passive"))
      (node (ref "U23") (pin "6") (pinfunction "INB-_6") (pintype "input"))
    )
    (net (code "43") (name "Net-(U24-CAP-)") (class "Default")
      (node (ref "C89") (pin "1") (pinfunction "1_1") (pintype "passive"))
      (node (ref "U24") (pin "28") (pinfunction "CAP-_28") (pintype "passive"))
    )
    (net (code "44") (name "Net-(U24-DEC+)") (class "Default")
      (node (ref "C90") (pin "2") (pinfunction "2_2") (pintype "passive"))
      (node (ref "U24") (pin "20") (pinfunction "DEC+_20") (pintype "passive"))
    )
    (net (code "45") (name "Net-(U24-DEC-)") (class "Default")
      (node (ref "C90") (pin "1") (pinfunction "1_1") (pintype "passive"))
      (node (ref "U24") (pin "21") (pinfunction "DEC-_21") (pintype "passive"))
    )
    (net (code "46") (name "Net-(U24-GAIN1)") (class "Default")
      (node (ref "R125") (pin "2") (pinfunction "2_2") (pintype "passive"))
      (node (ref "U24") (pin "5") (pinfunction "GAIN1_5") (pintype "passive"))
    )
    (net (code "47") (name "Net-(U24-THERM)") (class "Default")
      (node (ref "R120") (pin "2") (pinfunction "2_2") (pintype "passive"))
      (node (ref "R121") (pin "2") (pinfunction "2_2") (pintype "passive"))
      (node (ref "U24") (pin "1") (pinfunction "THERM_1") (pintype "passive"))
    )
    (net (code "48") (name "Net-(U24-THERMADJ1)") (class "Default")
      (node (ref "R120") (pin "1") (pinfunction "1_1") (pintype "passive"))
      (node (ref "R121") (pin "1") (pinfunction "1_1") (pintype "passive"))
      (node (ref "R122") (pin "1") (pinfunction "1_1") (pintype "passive"))
      (node (ref "U24") (pin "2") (pinfunction "THERMADJ1_2") (pintype "passive"))
    )
    (net (code "49") (name "Net-(U24-THERMADJ2)") (class "Default")
      (node (ref "R122") (pin "2") (pinfunction "2_2") (pintype "passive"))
      (node (ref "U24") (pin "3") (pinfunction "THERMADJ2_3") (pintype "passive"))
    )
    (net (code "50") (name "unconnected-(U22-2.5V-Pad13)") (class "Default")
      (node (ref "U22") (pin "13") (pinfunction "2.5V_13") (pintype "passive+no_connect"))
    )
    (net (code "51") (name "unconnected-(U22-NC-Pad4)") (class "Default")
      (node (ref "U22") (pin "4") (pinfunction "NC_4") (pintype "passive+no_connect"))
    )
    (net (code "52") (name "unconnected-(U22-NC-Pad15)") (class "Default")
      (node (ref "U22") (pin "15") (pinfunction "NC_15") (pintype "passive+no_connect"))
    )
    (net (code "53") (name "unconnected-(U22-NC-Pad16)") (class "Default")
      (node (ref "U22") (pin "16") (pinfunction "NC_16") (pintype "passive+no_connect"))
    )
    (net (code "54") (name "unconnected-(U22-NC-Pad23)") (class "Default")
      (node (ref "U22") (pin "23") (pinfunction "NC_23") (pintype "passive+no_connect"))
    )
    (net (code "55") (name "unconnected-(U22-NULLAD-Pad26)") (class "Default")
      (node (ref "U22") (pin "26") (pinfunction "NULLAD_26") (pintype "passive+no_connect"))
    )
    (net (code "56") (name "unconnected-(U22-OFFMAX-Pad14)") (class "Default")
      (node (ref "U22") (pin "14") (pinfunction "OFFMAX_14") (pintype "passive+no_connect"))
    )
    (net (code "57") (name "unconnected-(U22-VRADJ-Pad8)") (class "Default")
      (node (ref "U22") (pin "8") (pinfunction "VRADJ_8") (pintype "passive+no_connect"))
    )
    (net (code "58") (name "unconnected-(U24-2.5V-Pad13)") (class "Default")
      (node (ref "U24") (pin "13") (pinfunction "2.5V_13") (pintype "passive+no_connect"))
    )
    (net (code "59") (name "unconnected-(U24-NC-Pad4)") (class "Default")
      (node (ref "U24") (pin "4") (pinfunction "NC_4") (pintype "passive+no_connect"))
    )
    (net (code "60") (name "unconnected-(U24-NC-Pad15)") (class "Default")
      (node (ref "U24") (pin "15") (pinfunction "NC_15") (pintype "passive+no_connect"))
    )
    (net (code "61") (name "unconnected-(U24-NC-Pad16)") (class "Default")
      (node (ref "U24") (pin "16") (pinfunction "NC_16") (pintype "passive+no_connect"))
    )
    (net (code "62") (name "unconnected-(U24-NC-Pad23)") (class "Default")
      (node (ref "U24") (pin "23") (pinfunction "NC_23") (pintype "passive+no_connect"))
    )
    (net (code "63") (name "unconnected-(U24-NULLAD-Pad26)") (class "Default")
      (node (ref "U24") (pin "26") (pinfunction "NULLAD_26") (pintype "passive+no_connect"))
    )
    (net (code "64") (name "unconnected-(U24-OFFMAX-Pad14)") (class "Default")
      (node (ref "U24") (pin "14") (pinfunction "OFFMAX_14") (pintype "passive+no_connect"))
    )
    (net (code "65") (name "unconnected-(U24-VRADJ-Pad8)") (class "Default")
      (node (ref "U24") (pin "8") (pinfunction "VRADJ_8") (pintype "passive+no_connect"))
    )
  )
)
